# ROBOT.net
KiCad netlist of a schematic drawn in EAGLE
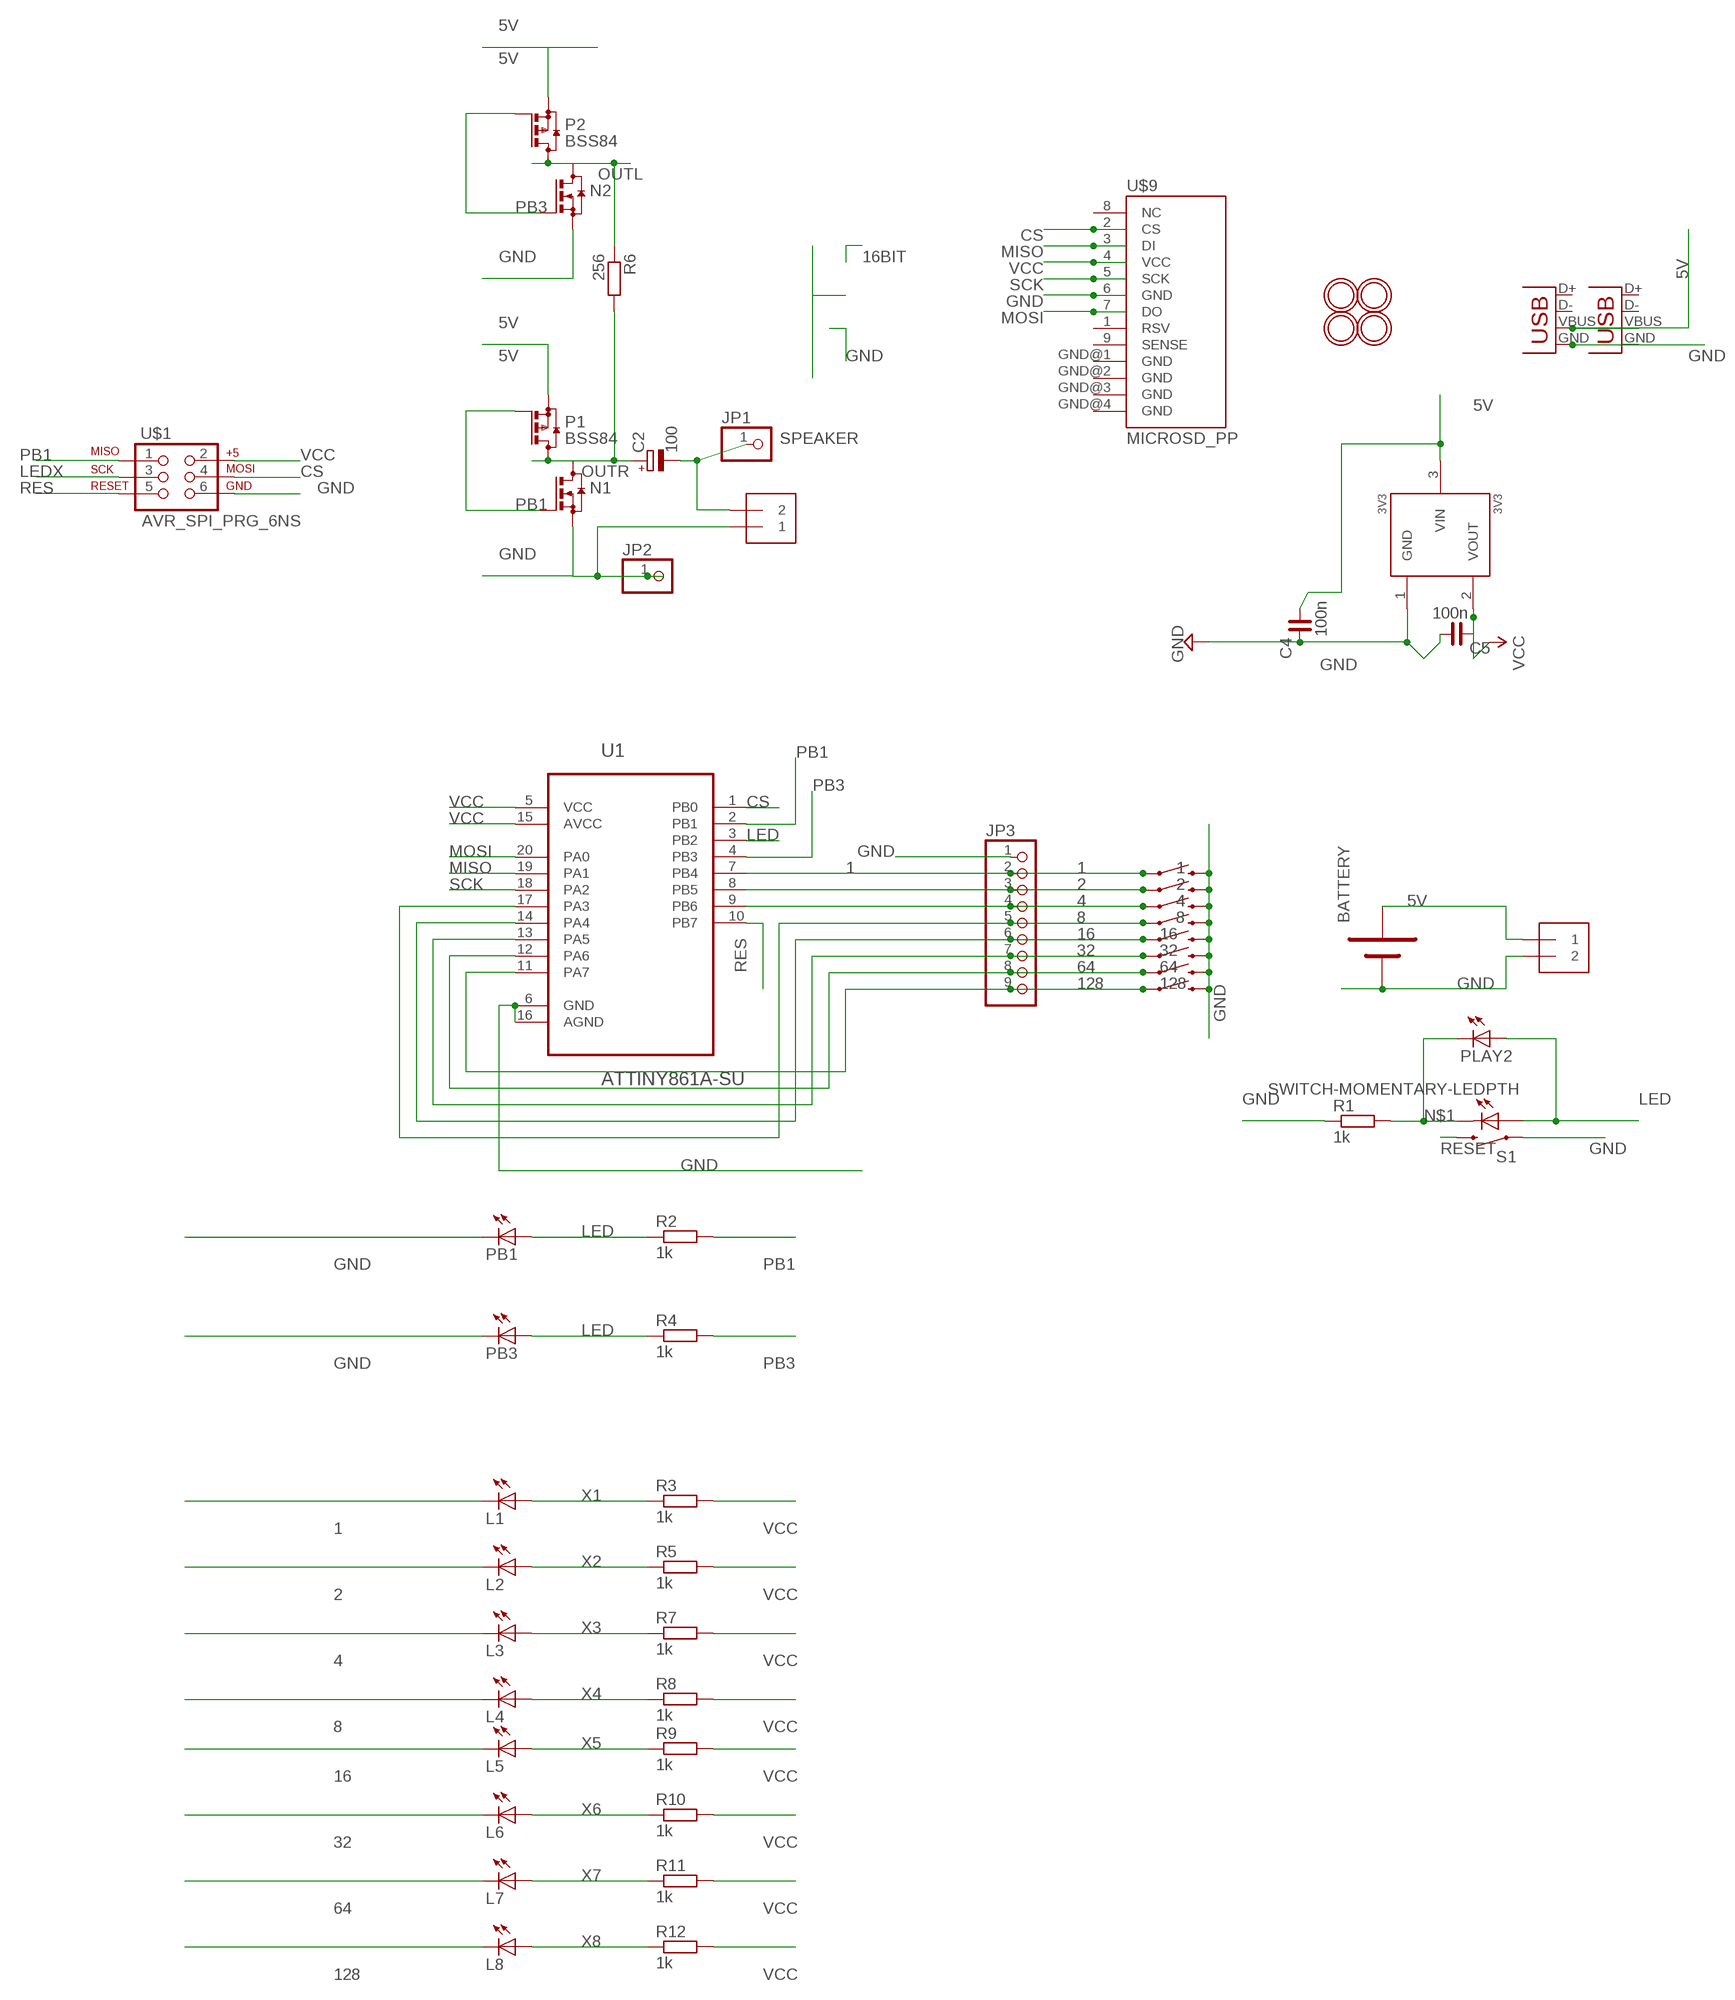
[diagram p0: schematic, sheet 1]

(export (version "E")
  (design (tool "Eeschema 10.0.6"))
  (components
    (comp (ref "1")
      (value "SWITCH-MOMENTARY-2-SMD-1101NE")
      (footprint "eagle-import:TACTILE-SWITCH-1101NE")
      (libsource (lib "eagle-import") (part "SWITCH-MOMENTARY-2-SMD-1101NE"))
    )
    (comp (ref "2")
      (value "SWITCH-MOMENTARY-2-SMD-1101NE")
      (footprint "eagle-import:TACTILE-SWITCH-1101NE")
      (libsource (lib "eagle-import") (part "SWITCH-MOMENTARY-2-SMD-1101NE"))
    )
    (comp (ref "3V3")
      (value "3V3")
      (footprint "eagle-import:SOT23")
      (libsource (lib "eagle-import") (part "MCP1700T"))
    )
    (comp (ref "4")
      (value "SWITCH-MOMENTARY-2-SMD-1101NE")
      (footprint "eagle-import:TACTILE-SWITCH-1101NE")
      (libsource (lib "eagle-import") (part "SWITCH-MOMENTARY-2-SMD-1101NE"))
    )
    (comp (ref "8")
      (value "SWITCH-MOMENTARY-2-SMD-1101NE")
      (footprint "eagle-import:TACTILE-SWITCH-1101NE")
      (libsource (lib "eagle-import") (part "SWITCH-MOMENTARY-2-SMD-1101NE"))
    )
    (comp (ref "16")
      (value "SWITCH-MOMENTARY-2-SMD-1101NE")
      (footprint "eagle-import:TACTILE-SWITCH-1101NE")
      (libsource (lib "eagle-import") (part "SWITCH-MOMENTARY-2-SMD-1101NE"))
    )
    (comp (ref "32")
      (value "SWITCH-MOMENTARY-2-SMD-1101NE")
      (footprint "eagle-import:TACTILE-SWITCH-1101NE")
      (libsource (lib "eagle-import") (part "SWITCH-MOMENTARY-2-SMD-1101NE"))
    )
    (comp (ref "64")
      (value "SWITCH-MOMENTARY-2-SMD-1101NE")
      (footprint "eagle-import:TACTILE-SWITCH-1101NE")
      (libsource (lib "eagle-import") (part "SWITCH-MOMENTARY-2-SMD-1101NE"))
    )
    (comp (ref "128")
      (value "SWITCH-MOMENTARY-2-SMD-1101NE")
      (footprint "eagle-import:TACTILE-SWITCH-1101NE")
      (libsource (lib "eagle-import") (part "SWITCH-MOMENTARY-2-SMD-1101NE"))
    )
    (comp (ref "BATTERY")
      (value "BATTERY-1XAA20MM")
      (footprint "eagle-import:BATTCOM_20MM_PTH")
      (libsource (lib "eagle-import") (part "BATTERY-1XAA20MM"))
    )
    (comp (ref "C2")
      (value "100")
      (footprint "eagle-import:153CLV-0605")
      (libsource (lib "eagle-import") (part "CPOL-EU153CLV-0605"))
    )
    (comp (ref "C4")
      (value "100n")
      (footprint "eagle-import:C0603")
      (libsource (lib "eagle-import") (part "C_0603"))
    )
    (comp (ref "C5")
      (value "100n")
      (footprint "eagle-import:C0603")
      (libsource (lib "eagle-import") (part "C_0603"))
    )
    (comp (ref "J1")
      (value "1X2-3.5MM")
      (footprint "eagle-import:1X2-3.5MM")
      (libsource (lib "eagle-import") (part "1X2-3.5MM"))
    )
    (comp (ref "J2")
      (value "1X2-3.5MM")
      (footprint "eagle-import:1X2-3.5MM")
      (libsource (lib "eagle-import") (part "1X2-3.5MM"))
    )
    (comp (ref "JP1")
      (value "PINHD-1X1")
      (footprint "eagle-import:1X01")
      (libsource (lib "eagle-import") (part "PINHD-1X1"))
    )
    (comp (ref "JP2")
      (value "PINHD-1X1")
      (footprint "eagle-import:1X01")
      (libsource (lib "eagle-import") (part "PINHD-1X1"))
    )
    (comp (ref "JP3")
      (value "PINHD-1X9")
      (footprint "eagle-import:1X09")
      (libsource (lib "eagle-import") (part "PINHD-1X9"))
    )
    (comp (ref "L1")
      (value "LEDSML0603")
      (footprint "eagle-import:SML0603")
      (libsource (lib "eagle-import") (part "LEDSML0603"))
    )
    (comp (ref "L2")
      (value "LEDSML0603")
      (footprint "eagle-import:SML0603")
      (libsource (lib "eagle-import") (part "LEDSML0603"))
    )
    (comp (ref "L3")
      (value "LEDSML0603")
      (footprint "eagle-import:SML0603")
      (libsource (lib "eagle-import") (part "LEDSML0603"))
    )
    (comp (ref "L4")
      (value "LEDSML0603")
      (footprint "eagle-import:SML0603")
      (libsource (lib "eagle-import") (part "LEDSML0603"))
    )
    (comp (ref "L5")
      (value "LEDSML0603")
      (footprint "eagle-import:SML0603")
      (libsource (lib "eagle-import") (part "LEDSML0603"))
    )
    (comp (ref "L6")
      (value "LEDSML0603")
      (footprint "eagle-import:SML0603")
      (libsource (lib "eagle-import") (part "LEDSML0603"))
    )
    (comp (ref "L7")
      (value "LEDSML0603")
      (footprint "eagle-import:SML0603")
      (libsource (lib "eagle-import") (part "LEDSML0603"))
    )
    (comp (ref "L8")
      (value "LEDSML0603")
      (footprint "eagle-import:SML0603")
      (libsource (lib "eagle-import") (part "LEDSML0603"))
    )
    (comp (ref "N1")
      (value "BSS123")
      (footprint "eagle-import:SOT23")
      (libsource (lib "eagle-import") (part "BSS123"))
    )
    (comp (ref "N2")
      (value "BSS123")
      (footprint "eagle-import:SOT23")
      (libsource (lib "eagle-import") (part "BSS123"))
    )
    (comp (ref "P1")
      (value "BSS84")
      (footprint "eagle-import:SOT23")
      (libsource (lib "eagle-import") (part "BSS84"))
    )
    (comp (ref "P2")
      (value "BSS84")
      (footprint "eagle-import:SOT23")
      (libsource (lib "eagle-import") (part "BSS84"))
    )
    (comp (ref "PB1")
      (value "LEDSML0603")
      (footprint "eagle-import:SML0603")
      (libsource (lib "eagle-import") (part "LEDSML0603"))
    )
    (comp (ref "PB3")
      (value "LEDSML0603")
      (footprint "eagle-import:SML0603")
      (libsource (lib "eagle-import") (part "LEDSML0603"))
    )
    (comp (ref "PLAY2")
      (value "LEDSML0603")
      (footprint "eagle-import:SML0603")
      (libsource (lib "eagle-import") (part "LEDSML0603"))
    )
    (comp (ref "R1")
      (value "1k")
      (footprint "eagle-import:R0603")
      (libsource (lib "eagle-import") (part "R-EU_R0603"))
    )
    (comp (ref "R2")
      (value "1k")
      (footprint "eagle-import:R0603")
      (libsource (lib "eagle-import") (part "R-EU_R0603"))
    )
    (comp (ref "R3")
      (value "1k")
      (footprint "eagle-import:R0603")
      (libsource (lib "eagle-import") (part "R-EU_R0603"))
    )
    (comp (ref "R4")
      (value "1k")
      (footprint "eagle-import:R0603")
      (libsource (lib "eagle-import") (part "R-EU_R0603"))
    )
    (comp (ref "R5")
      (value "1k")
      (footprint "eagle-import:R0603")
      (libsource (lib "eagle-import") (part "R-EU_R0603"))
    )
    (comp (ref "R6")
      (value "256")
      (footprint "eagle-import:R0603")
      (libsource (lib "eagle-import") (part "R-EU_R0603"))
    )
    (comp (ref "R7")
      (value "1k")
      (footprint "eagle-import:R0603")
      (libsource (lib "eagle-import") (part "R-EU_R0603"))
    )
    (comp (ref "R8")
      (value "1k")
      (footprint "eagle-import:R0603")
      (libsource (lib "eagle-import") (part "R-EU_R0603"))
    )
    (comp (ref "R9")
      (value "1k")
      (footprint "eagle-import:R0603")
      (libsource (lib "eagle-import") (part "R-EU_R0603"))
    )
    (comp (ref "R10")
      (value "1k")
      (footprint "eagle-import:R0603")
      (libsource (lib "eagle-import") (part "R-EU_R0603"))
    )
    (comp (ref "R11")
      (value "1k")
      (footprint "eagle-import:R0603")
      (libsource (lib "eagle-import") (part "R-EU_R0603"))
    )
    (comp (ref "R12")
      (value "1k")
      (footprint "eagle-import:R0603")
      (libsource (lib "eagle-import") (part "R-EU_R0603"))
    )
    (comp (ref "S1")
      (value "SWITCH-MOMENTARY-LEDPTH")
      (footprint "eagle-import:TACTILE-PTH-LED-12MM")
      (libsource (lib "eagle-import") (part "SWITCH-MOMENTARY-LEDPTH"))
    )
    (comp (ref "U$1")
      (value "AVR_SPI_PRG_6NS")
      (footprint "eagle-import:2X3-NS")
      (libsource (lib "eagle-import") (part "AVR_SPI_PRG_6NS"))
    )
    (comp (ref "U$3")
      (value "MOUNTINGHOLE1.0")
      (footprint "eagle-import:MOUNTINGHOLE_1.0_PLATED")
      (libsource (lib "eagle-import") (part "MOUNTINGHOLE1.0"))
    )
    (comp (ref "U$4")
      (value "MOUNTINGHOLE1.0")
      (footprint "eagle-import:MOUNTINGHOLE_1.0_PLATED")
      (libsource (lib "eagle-import") (part "MOUNTINGHOLE1.0"))
    )
    (comp (ref "U$6")
      (value "MOUNTINGHOLE3.0THIN")
      (footprint "eagle-import:MOUNTINGHOLE_3.0_PLATEDTHIN")
      (libsource (lib "eagle-import") (part "MOUNTINGHOLE3.0THIN"))
    )
    (comp (ref "U$7")
      (value "MOUNTINGHOLE3.0THIN")
      (footprint "eagle-import:MOUNTINGHOLE_3.0_PLATEDTHIN")
      (libsource (lib "eagle-import") (part "MOUNTINGHOLE3.0THIN"))
    )
    (comp (ref "U$9")
      (value "MICROSD_PP")
      (footprint "eagle-import:MICROSD_PP")
      (libsource (lib "eagle-import") (part "MICROSD_PP"))
    )
    (comp (ref "U1")
      (value "ATTINY861A-SU")
      (footprint "eagle-import:SOIC127P1032X265-20N")
      (libsource (lib "eagle-import") (part "ATTINY861A-SU"))
    )
    (comp (ref "X1")
      (value "USB-MICROB")
      (footprint "eagle-import:USB-MICROB")
      (libsource (lib "eagle-import") (part "USB-MICROB"))
    )
    (comp (ref "X5")
      (value "USBSMD")
      (footprint "eagle-import:USB-MINIB")
      (libsource (lib "eagle-import") (part "USBSMD"))
    )
  )
  (nets
    (net (code "1") (name "/1") (class "Default")
      (node (ref "1") (pin "P$1") (pinfunction "1_P$1") (pintype "passive"))
      (node (ref "JP3") (pin "2") (pinfunction "2_2") (pintype "passive"))
      (node (ref "L1") (pin "C") (pinfunction "C_C") (pintype "passive"))
      (node (ref "U1") (pin "7") (pinfunction "PB4_7") (pintype "bidirectional"))
    )
    (net (code "2") (name "/2") (class "Default")
      (node (ref "2") (pin "P$1") (pinfunction "1_P$1") (pintype "passive"))
      (node (ref "JP3") (pin "3") (pinfunction "3_3") (pintype "passive"))
      (node (ref "L2") (pin "C") (pinfunction "C_C") (pintype "passive"))
      (node (ref "U1") (pin "8") (pinfunction "PB5_8") (pintype "bidirectional"))
    )
    (net (code "3") (name "/4") (class "Default")
      (node (ref "4") (pin "P$1") (pinfunction "1_P$1") (pintype "passive"))
      (node (ref "JP3") (pin "4") (pinfunction "4_4") (pintype "passive"))
      (node (ref "L3") (pin "C") (pinfunction "C_C") (pintype "passive"))
      (node (ref "U1") (pin "9") (pinfunction "PB6_9") (pintype "bidirectional"))
    )
    (net (code "4") (name "/5V") (class "Default")
      (node (ref "3V3") (pin "3") (pinfunction "VIN_3") (pintype "bidirectional"))
      (node (ref "BATTERY") (pin "+") (pinfunction "+_+") (pintype "bidirectional"))
      (node (ref "C4") (pin "1") (pinfunction "1_1") (pintype "passive"))
      (node (ref "J2") (pin "1") (pinfunction "1_1") (pintype "passive"))
      (node (ref "P1") (pin "2") (pinfunction "S_2") (pintype "passive"))
      (node (ref "P2") (pin "2") (pinfunction "S_2") (pintype "passive"))
      (node (ref "X1") (pin "VBUS") (pinfunction "VBUS_VBUS") (pintype "bidirectional"))
      (node (ref "X5") (pin "VBUS") (pinfunction "VBUS_VBUS") (pintype "bidirectional"))
    )
    (net (code "5") (name "/8") (class "Default")
      (node (ref "8") (pin "P$1") (pinfunction "1_P$1") (pintype "passive"))
      (node (ref "JP3") (pin "5") (pinfunction "5_5") (pintype "passive"))
      (node (ref "L4") (pin "C") (pinfunction "C_C") (pintype "passive"))
      (node (ref "U1") (pin "17") (pinfunction "PA3_17") (pintype "bidirectional"))
    )
    (net (code "6") (name "/16") (class "Default")
      (node (ref "16") (pin "P$1") (pinfunction "1_P$1") (pintype "passive"))
      (node (ref "JP3") (pin "6") (pinfunction "6_6") (pintype "passive"))
      (node (ref "L5") (pin "C") (pinfunction "C_C") (pintype "passive"))
      (node (ref "U1") (pin "14") (pinfunction "PA4_14") (pintype "bidirectional"))
    )
    (net (code "8") (name "/32") (class "Default")
      (node (ref "32") (pin "P$1") (pinfunction "1_P$1") (pintype "passive"))
      (node (ref "JP3") (pin "7") (pinfunction "7_7") (pintype "passive"))
      (node (ref "L6") (pin "C") (pinfunction "C_C") (pintype "passive"))
      (node (ref "U1") (pin "13") (pinfunction "PA5_13") (pintype "bidirectional"))
    )
    (net (code "9") (name "/64") (class "Default")
      (node (ref "64") (pin "P$1") (pinfunction "1_P$1") (pintype "passive"))
      (node (ref "JP3") (pin "8") (pinfunction "8_8") (pintype "passive"))
      (node (ref "L7") (pin "C") (pinfunction "C_C") (pintype "passive"))
      (node (ref "U1") (pin "12") (pinfunction "PA6_12") (pintype "bidirectional"))
    )
    (net (code "10") (name "/128") (class "Default")
      (node (ref "128") (pin "P$1") (pinfunction "1_P$1") (pintype "passive"))
      (node (ref "JP3") (pin "9") (pinfunction "9_9") (pintype "passive"))
      (node (ref "L8") (pin "C") (pinfunction "C_C") (pintype "passive"))
      (node (ref "U1") (pin "11") (pinfunction "PA7_11") (pintype "bidirectional"))
    )
    (net (code "11") (name "/CS") (class "Default")
      (node (ref "U$1") (pin "4") (pinfunction "4_4") (pintype "passive"))
      (node (ref "U$9") (pin "2") (pinfunction "CS_2") (pintype "bidirectional"))
      (node (ref "U1") (pin "1") (pinfunction "PB0_1") (pintype "bidirectional"))
    )
    (net (code "12") (name "/LED") (class "Default")
      (node (ref "PB1") (pin "A") (pinfunction "A_A") (pintype "passive"))
      (node (ref "PB3") (pin "A") (pinfunction "A_A") (pintype "passive"))
      (node (ref "PLAY2") (pin "A") (pinfunction "A_A") (pintype "passive"))
      (node (ref "R2") (pin "1") (pinfunction "1_1") (pintype "passive"))
      (node (ref "R4") (pin "1") (pinfunction "1_1") (pintype "passive"))
      (node (ref "S1") (pin "A") (pinfunction "A_A") (pintype "passive"))
      (node (ref "U1") (pin "3") (pinfunction "PB2_3") (pintype "bidirectional"))
    )
    (net (code "13") (name "/LEDX") (class "Default")
      (node (ref "U$1") (pin "3") (pinfunction "3_3") (pintype "passive"))
    )
    (net (code "14") (name "/MISO") (class "Default")
      (node (ref "U$9") (pin "3") (pinfunction "DI_3") (pintype "bidirectional"))
      (node (ref "U1") (pin "19") (pinfunction "PA1_19") (pintype "bidirectional"))
    )
    (net (code "15") (name "/MOSI") (class "Default")
      (node (ref "U$9") (pin "7") (pinfunction "DO_7") (pintype "bidirectional"))
      (node (ref "U1") (pin "20") (pinfunction "PA0_20") (pintype "bidirectional"))
    )
    (net (code "16") (name "/N$1") (class "Default")
      (node (ref "PLAY2") (pin "C") (pinfunction "C_C") (pintype "passive"))
      (node (ref "R1") (pin "2") (pinfunction "2_2") (pintype "passive"))
      (node (ref "S1") (pin "C") (pinfunction "C_C") (pintype "passive"))
    )
    (net (code "17") (name "/OUTL") (class "Default")
      (node (ref "N2") (pin "3") (pinfunction "D_3") (pintype "passive"))
      (node (ref "P2") (pin "3") (pinfunction "D_3") (pintype "passive"))
      (node (ref "R6") (pin "1") (pinfunction "1_1") (pintype "passive"))
    )
    (net (code "18") (name "/OUTR") (class "Default")
      (node (ref "C2") (pin "+") (pinfunction "+_+") (pintype "passive"))
      (node (ref "N1") (pin "3") (pinfunction "D_3") (pintype "passive"))
      (node (ref "P1") (pin "3") (pinfunction "D_3") (pintype "passive"))
      (node (ref "R6") (pin "2") (pinfunction "2_2") (pintype "passive"))
    )
    (net (code "19") (name "/PB1") (class "Default")
      (node (ref "N1") (pin "1") (pinfunction "G_1") (pintype "passive"))
      (node (ref "P1") (pin "1") (pinfunction "G_1") (pintype "passive"))
      (node (ref "R2") (pin "2") (pinfunction "2_2") (pintype "passive"))
      (node (ref "U$1") (pin "1") (pinfunction "1_1") (pintype "passive"))
      (node (ref "U1") (pin "2") (pinfunction "PB1_2") (pintype "bidirectional"))
    )
    (net (code "20") (name "/PB3") (class "Default")
      (node (ref "N2") (pin "1") (pinfunction "G_1") (pintype "passive"))
      (node (ref "P2") (pin "1") (pinfunction "G_1") (pintype "passive"))
      (node (ref "R4") (pin "2") (pinfunction "2_2") (pintype "passive"))
      (node (ref "U1") (pin "4") (pinfunction "PB3_4") (pintype "bidirectional"))
    )
    (net (code "21") (name "/RES") (class "Default")
      (node (ref "U$1") (pin "5") (pinfunction "5_5") (pintype "passive"))
      (node (ref "U1") (pin "10") (pinfunction "PB7_10") (pintype "bidirectional"))
    )
    (net (code "22") (name "/RESET") (class "Default")
      (node (ref "S1") (pin "2") (pinfunction "2_2") (pintype "passive"))
    )
    (net (code "23") (name "/SCK") (class "Default")
      (node (ref "U$9") (pin "5") (pinfunction "SCK_5") (pintype "bidirectional"))
      (node (ref "U1") (pin "18") (pinfunction "PA2_18") (pintype "bidirectional"))
    )
    (net (code "24") (name "/SPEAKER") (class "Default")
      (node (ref "C2") (pin "-") (pinfunction "-_-") (pintype "passive"))
      (node (ref "J1") (pin "2") (pinfunction "2_2") (pintype "passive"))
      (node (ref "JP1") (pin "1") (pinfunction "1_1") (pintype "passive"))
    )
    (net (code "25") (name "/X1") (class "Default")
      (node (ref "L1") (pin "A") (pinfunction "A_A") (pintype "passive"))
      (node (ref "R3") (pin "1") (pinfunction "1_1") (pintype "passive"))
    )
    (net (code "26") (name "/X2") (class "Default")
      (node (ref "L2") (pin "A") (pinfunction "A_A") (pintype "passive"))
      (node (ref "R5") (pin "1") (pinfunction "1_1") (pintype "passive"))
    )
    (net (code "27") (name "/X3") (class "Default")
      (node (ref "L3") (pin "A") (pinfunction "A_A") (pintype "passive"))
      (node (ref "R7") (pin "1") (pinfunction "1_1") (pintype "passive"))
    )
    (net (code "28") (name "/X4") (class "Default")
      (node (ref "L4") (pin "A") (pinfunction "A_A") (pintype "passive"))
      (node (ref "R8") (pin "1") (pinfunction "1_1") (pintype "passive"))
    )
    (net (code "29") (name "/X5") (class "Default")
      (node (ref "L5") (pin "A") (pinfunction "A_A") (pintype "passive"))
      (node (ref "R9") (pin "1") (pinfunction "1_1") (pintype "passive"))
    )
    (net (code "30") (name "/X6") (class "Default")
      (node (ref "L6") (pin "A") (pinfunction "A_A") (pintype "passive"))
      (node (ref "R10") (pin "1") (pinfunction "1_1") (pintype "passive"))
    )
    (net (code "31") (name "/X7") (class "Default")
      (node (ref "L7") (pin "A") (pinfunction "A_A") (pintype "passive"))
      (node (ref "R11") (pin "1") (pinfunction "1_1") (pintype "passive"))
    )
    (net (code "32") (name "/X8") (class "Default")
      (node (ref "L8") (pin "A") (pinfunction "A_A") (pintype "passive"))
      (node (ref "R12") (pin "1") (pinfunction "1_1") (pintype "passive"))
    )
    (net (code "33") (name "GND") (class "Default")
      (node (ref "1") (pin "P$2") (pinfunction "2_P$2") (pintype "passive"))
      (node (ref "128") (pin "P$2") (pinfunction "2_P$2") (pintype "passive"))
      (node (ref "16") (pin "P$2") (pinfunction "2_P$2") (pintype "passive"))
      (node (ref "2") (pin "P$2") (pinfunction "2_P$2") (pintype "passive"))
      (node (ref "32") (pin "P$2") (pinfunction "2_P$2") (pintype "passive"))
      (node (ref "3V3") (pin "1") (pinfunction "GND_1") (pintype "bidirectional"))
      (node (ref "4") (pin "P$2") (pinfunction "2_P$2") (pintype "passive"))
      (node (ref "64") (pin "P$2") (pinfunction "2_P$2") (pintype "passive"))
      (node (ref "8") (pin "P$2") (pinfunction "2_P$2") (pintype "passive"))
      (node (ref "BATTERY") (pin "-") (pinfunction "-_-") (pintype "bidirectional"))
      (node (ref "C4") (pin "2") (pinfunction "2_2") (pintype "passive"))
      (node (ref "C5") (pin "1") (pinfunction "1_1") (pintype "passive"))
      (node (ref "J1") (pin "1") (pinfunction "1_1") (pintype "passive"))
      (node (ref "J2") (pin "2") (pinfunction "2_2") (pintype "passive"))
      (node (ref "JP2") (pin "1") (pinfunction "1_1") (pintype "passive"))
      (node (ref "JP3") (pin "1") (pinfunction "1_1") (pintype "passive"))
      (node (ref "N1") (pin "2") (pinfunction "S_2") (pintype "passive"))
      (node (ref "N2") (pin "2") (pinfunction "S_2") (pintype "passive"))
      (node (ref "PB1") (pin "C") (pinfunction "C_C") (pintype "passive"))
      (node (ref "PB3") (pin "C") (pinfunction "C_C") (pintype "passive"))
      (node (ref "R1") (pin "1") (pinfunction "1_1") (pintype "passive"))
      (node (ref "S1") (pin "4") (pinfunction "1_4") (pintype "passive"))
      (node (ref "U$1") (pin "6") (pinfunction "6_6") (pintype "passive"))
      (node (ref "U$9") (pin "6") (pinfunction "GND_6") (pintype "bidirectional"))
      (node (ref "U1") (pin "16") (pinfunction "AGND_16") (pintype "passive"))
      (node (ref "U1") (pin "6") (pinfunction "GND_6") (pintype "passive"))
      (node (ref "X1") (pin "GND") (pinfunction "GND_GND") (pintype "bidirectional"))
      (node (ref "X5") (pin "GND") (pinfunction "GND_GND") (pintype "bidirectional"))
    )
    (net (code "34") (name "VCC") (class "Default")
      (node (ref "3V3") (pin "2") (pinfunction "VOUT_2") (pintype "bidirectional"))
      (node (ref "C5") (pin "2") (pinfunction "2_2") (pintype "passive"))
      (node (ref "R10") (pin "2") (pinfunction "2_2") (pintype "passive"))
      (node (ref "R11") (pin "2") (pinfunction "2_2") (pintype "passive"))
      (node (ref "R12") (pin "2") (pinfunction "2_2") (pintype "passive"))
      (node (ref "R3") (pin "2") (pinfunction "2_2") (pintype "passive"))
      (node (ref "R5") (pin "2") (pinfunction "2_2") (pintype "passive"))
      (node (ref "R7") (pin "2") (pinfunction "2_2") (pintype "passive"))
      (node (ref "R8") (pin "2") (pinfunction "2_2") (pintype "passive"))
      (node (ref "R9") (pin "2") (pinfunction "2_2") (pintype "passive"))
      (node (ref "U$1") (pin "2") (pinfunction "2_2") (pintype "passive"))
      (node (ref "U$9") (pin "4") (pinfunction "VCC_4") (pintype "bidirectional"))
      (node (ref "U1") (pin "15") (pinfunction "AVCC_15") (pintype "power_in"))
      (node (ref "U1") (pin "5") (pinfunction "VCC_5") (pintype "power_in"))
    )
    (net (code "35") (name "unconnected-(U$9-GND-PadGND@1)") (class "Default")
      (node (ref "U$9") (pin "GND@1") (pinfunction "GND_GND@1") (pintype "bidirectional"))
    )
    (net (code "36") (name "unconnected-(U$9-GND-PadGND@2)") (class "Default")
      (node (ref "U$9") (pin "GND@2") (pinfunction "GND_GND@2") (pintype "bidirectional"))
    )
    (net (code "37") (name "unconnected-(U$9-GND-PadGND@3)") (class "Default")
      (node (ref "U$9") (pin "GND@3") (pinfunction "GND_GND@3") (pintype "bidirectional"))
    )
    (net (code "38") (name "unconnected-(U$9-GND-PadGND@4)") (class "Default")
      (node (ref "U$9") (pin "GND@4") (pinfunction "GND_GND@4") (pintype "bidirectional"))
    )
    (net (code "39") (name "unconnected-(U$9-NC-Pad8)") (class "Default")
      (node (ref "U$9") (pin "8") (pinfunction "NC_8") (pintype "bidirectional"))
    )
    (net (code "40") (name "unconnected-(U$9-RSV-Pad1)") (class "Default")
      (node (ref "U$9") (pin "1") (pinfunction "RSV_1") (pintype "bidirectional"))
    )
    (net (code "41") (name "unconnected-(U$9-SENSE-Pad9)") (class "Default")
      (node (ref "U$9") (pin "9") (pinfunction "SENSE_9") (pintype "bidirectional"))
    )
    (net (code "42") (name "unconnected-(X1-PadD+)") (class "Default")
      (node (ref "X1") (pin "D+") (pinfunction "D+_D+") (pintype "bidirectional"))
    )
    (net (code "43") (name "unconnected-(X1-PadD-)") (class "Default")
      (node (ref "X1") (pin "D-") (pinfunction "D-_D-") (pintype "bidirectional"))
    )
    (net (code "44") (name "unconnected-(X5-PadD+)") (class "Default")
      (node (ref "X5") (pin "D+") (pinfunction "D+_D+") (pintype "bidirectional"))
    )
    (net (code "45") (name "unconnected-(X5-PadD-)") (class "Default")
      (node (ref "X5") (pin "D-") (pinfunction "D-_D-") (pintype "bidirectional"))
    )
  )
)
